# 1-Schematic_polycard.net
KiCad netlist of a schematic drawn in EasyEDA
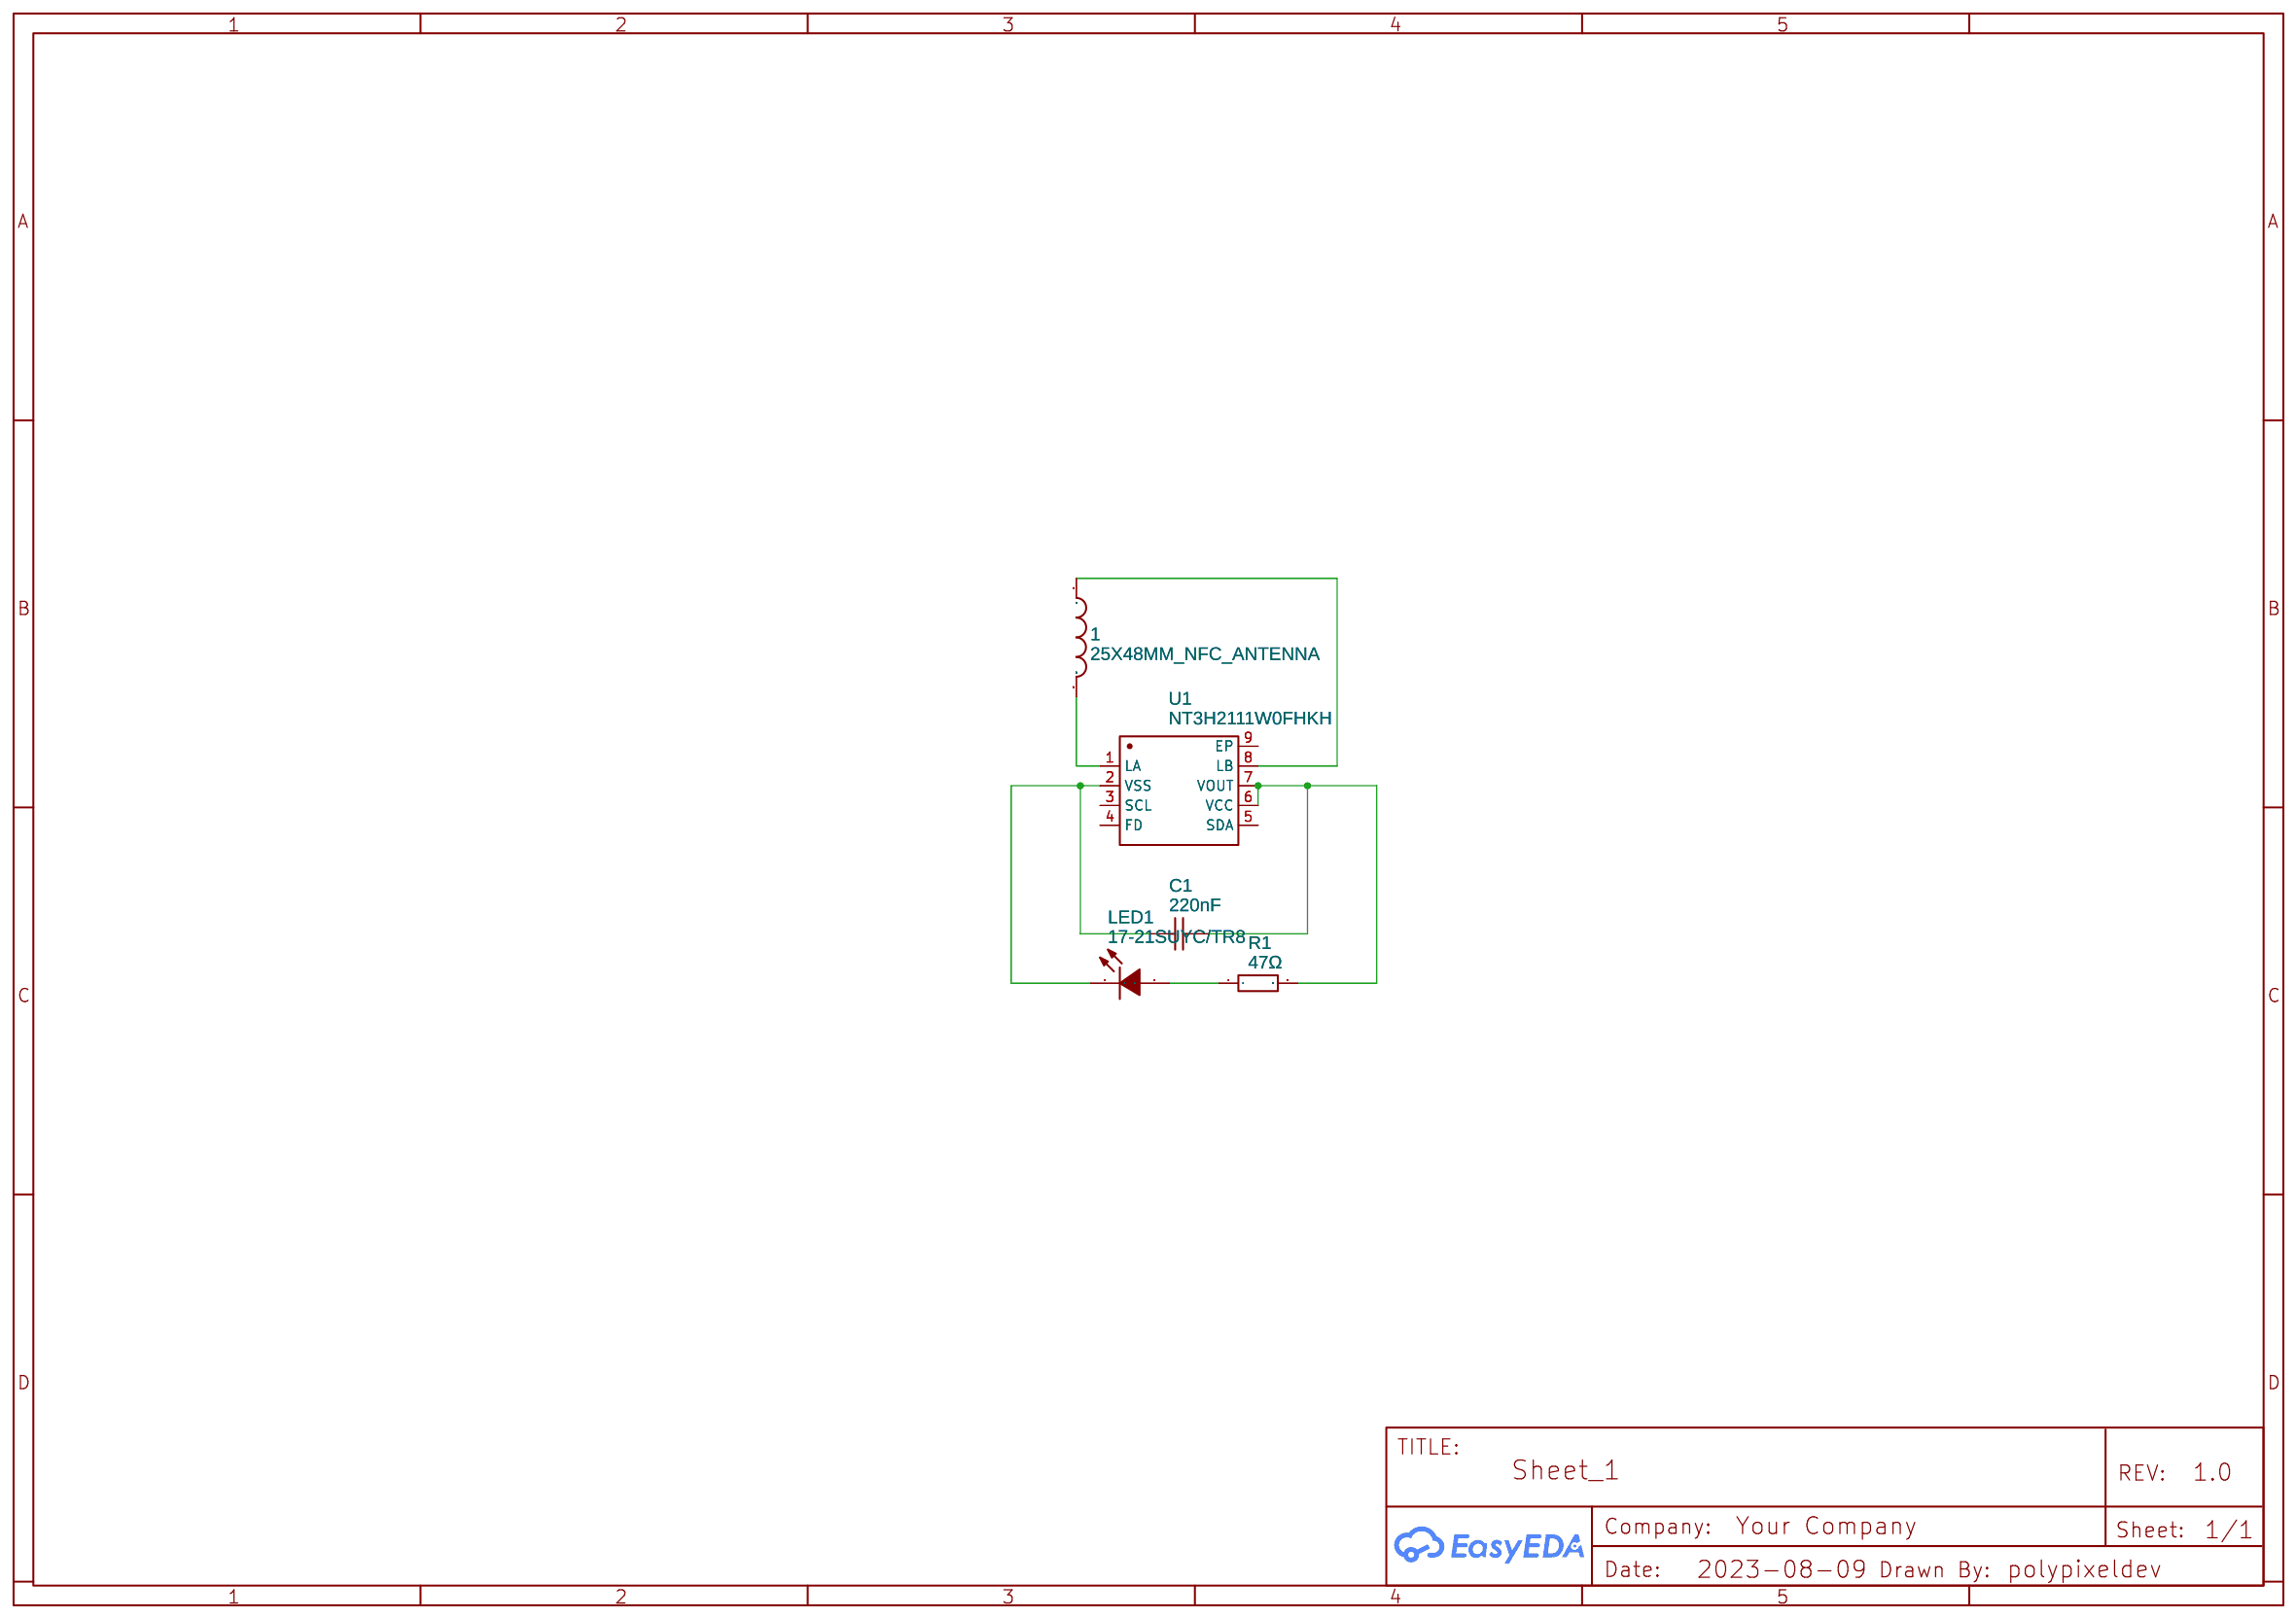
[diagram p0: schematic sheet]

(export (version "E")
  (design (tool "Eeschema 10.0.6"))
  (components
    (comp (ref "1") (value "25X48MM_NFC_ANTENNA") (libsource (lib "") (part "25X48MM_NFC_ANTENNA")))
    (comp (ref "C1")
      (value "220nF")
      (fields
        (field (name "Manufacturer Part") "CL10B224KA8NNNC")
        (field (name "Manufacturer") "SAMSUNG(三星)")
      )
      (libsource (lib "") (part "CL10B224KA8NNNC"))
    )
    (comp (ref "LED1")
      (value "17-21SUYC/TR8")
      (fields (field (name "Manufacturer Part") "KT-0805黄灯") (field (name "Manufacturer") "KENTO"))
      (libsource (lib "") (part "17-21SUYC/TR8"))
    )
    (comp (ref "R1")
      (value "47Ω")
      (fields
        (field (name "Manufacturer Part") "0603WAF470JT5E")
        (field (name "Manufacturer") "UNI-ROYAL(厚声)")
      )
      (libsource (lib "") (part "0603WAF470JT5E"))
    )
    (comp (ref "U1")
      (value "NT3H2111W0FHKH")
      (fields (field (name "Manufacturer") "NXP(恩智浦)"))
      (libsource (lib "") (part "NT3H2111W0FHKH"))
    )
  )
  (nets
    (net (code "1") (name "Net-(LED1-+)") (class "Default")
      (node (ref "LED1") (pin "1") (pinfunction "+_1") (pintype "unspecified"))
      (node (ref "R1") (pin "1") (pinfunction "1_1") (pintype "input"))
    )
    (net (code "2") (name "Net-(LED1--)") (class "Default")
      (node (ref "C1") (pin "1") (pinfunction "1_1") (pintype "input"))
      (node (ref "LED1") (pin "2") (pinfunction "-_2") (pintype "unspecified"))
      (node (ref "U1") (pin "2") (pinfunction "VSS_2") (pintype "unspecified"))
    )
    (net (code "3") (name "Net-(U1-LA)") (class "Default")
      (node (ref "1") (pin "P$2") (pinfunction "P$2_P$2") (pintype "bidirectional"))
      (node (ref "U1") (pin "1") (pinfunction "LA_1") (pintype "unspecified"))
    )
    (net (code "4") (name "Net-(U1-LB)") (class "Default")
      (node (ref "1") (pin "P$1") (pinfunction "P$1_P$1") (pintype "bidirectional"))
      (node (ref "U1") (pin "8") (pinfunction "LB_8") (pintype "unspecified"))
    )
    (net (code "5") (name "Net-(U1-VCC)") (class "Default")
      (node (ref "C1") (pin "2") (pinfunction "2_2") (pintype "input"))
      (node (ref "R1") (pin "2") (pinfunction "2_2") (pintype "input"))
      (node (ref "U1") (pin "6") (pinfunction "VCC_6") (pintype "unspecified"))
      (node (ref "U1") (pin "7") (pinfunction "VOUT_7") (pintype "unspecified"))
    )
    (net (code "6") (name "unconnected-(U1-EP-Pad9)") (class "Default")
      (node (ref "U1") (pin "9") (pinfunction "EP_9") (pintype "unspecified"))
    )
    (net (code "7") (name "unconnected-(U1-FD-Pad4)") (class "Default")
      (node (ref "U1") (pin "4") (pinfunction "FD_4") (pintype "unspecified"))
    )
    (net (code "8") (name "unconnected-(U1-SCL-Pad3)") (class "Default")
      (node (ref "U1") (pin "3") (pinfunction "SCL_3") (pintype "unspecified"))
    )
    (net (code "9") (name "unconnected-(U1-SDA-Pad5)") (class "Default")
      (node (ref "U1") (pin "5") (pinfunction "SDA_5") (pintype "unspecified"))
    )
  )
)
